# Clock2.net
KiCad netlist of a schematic drawn in EAGLE
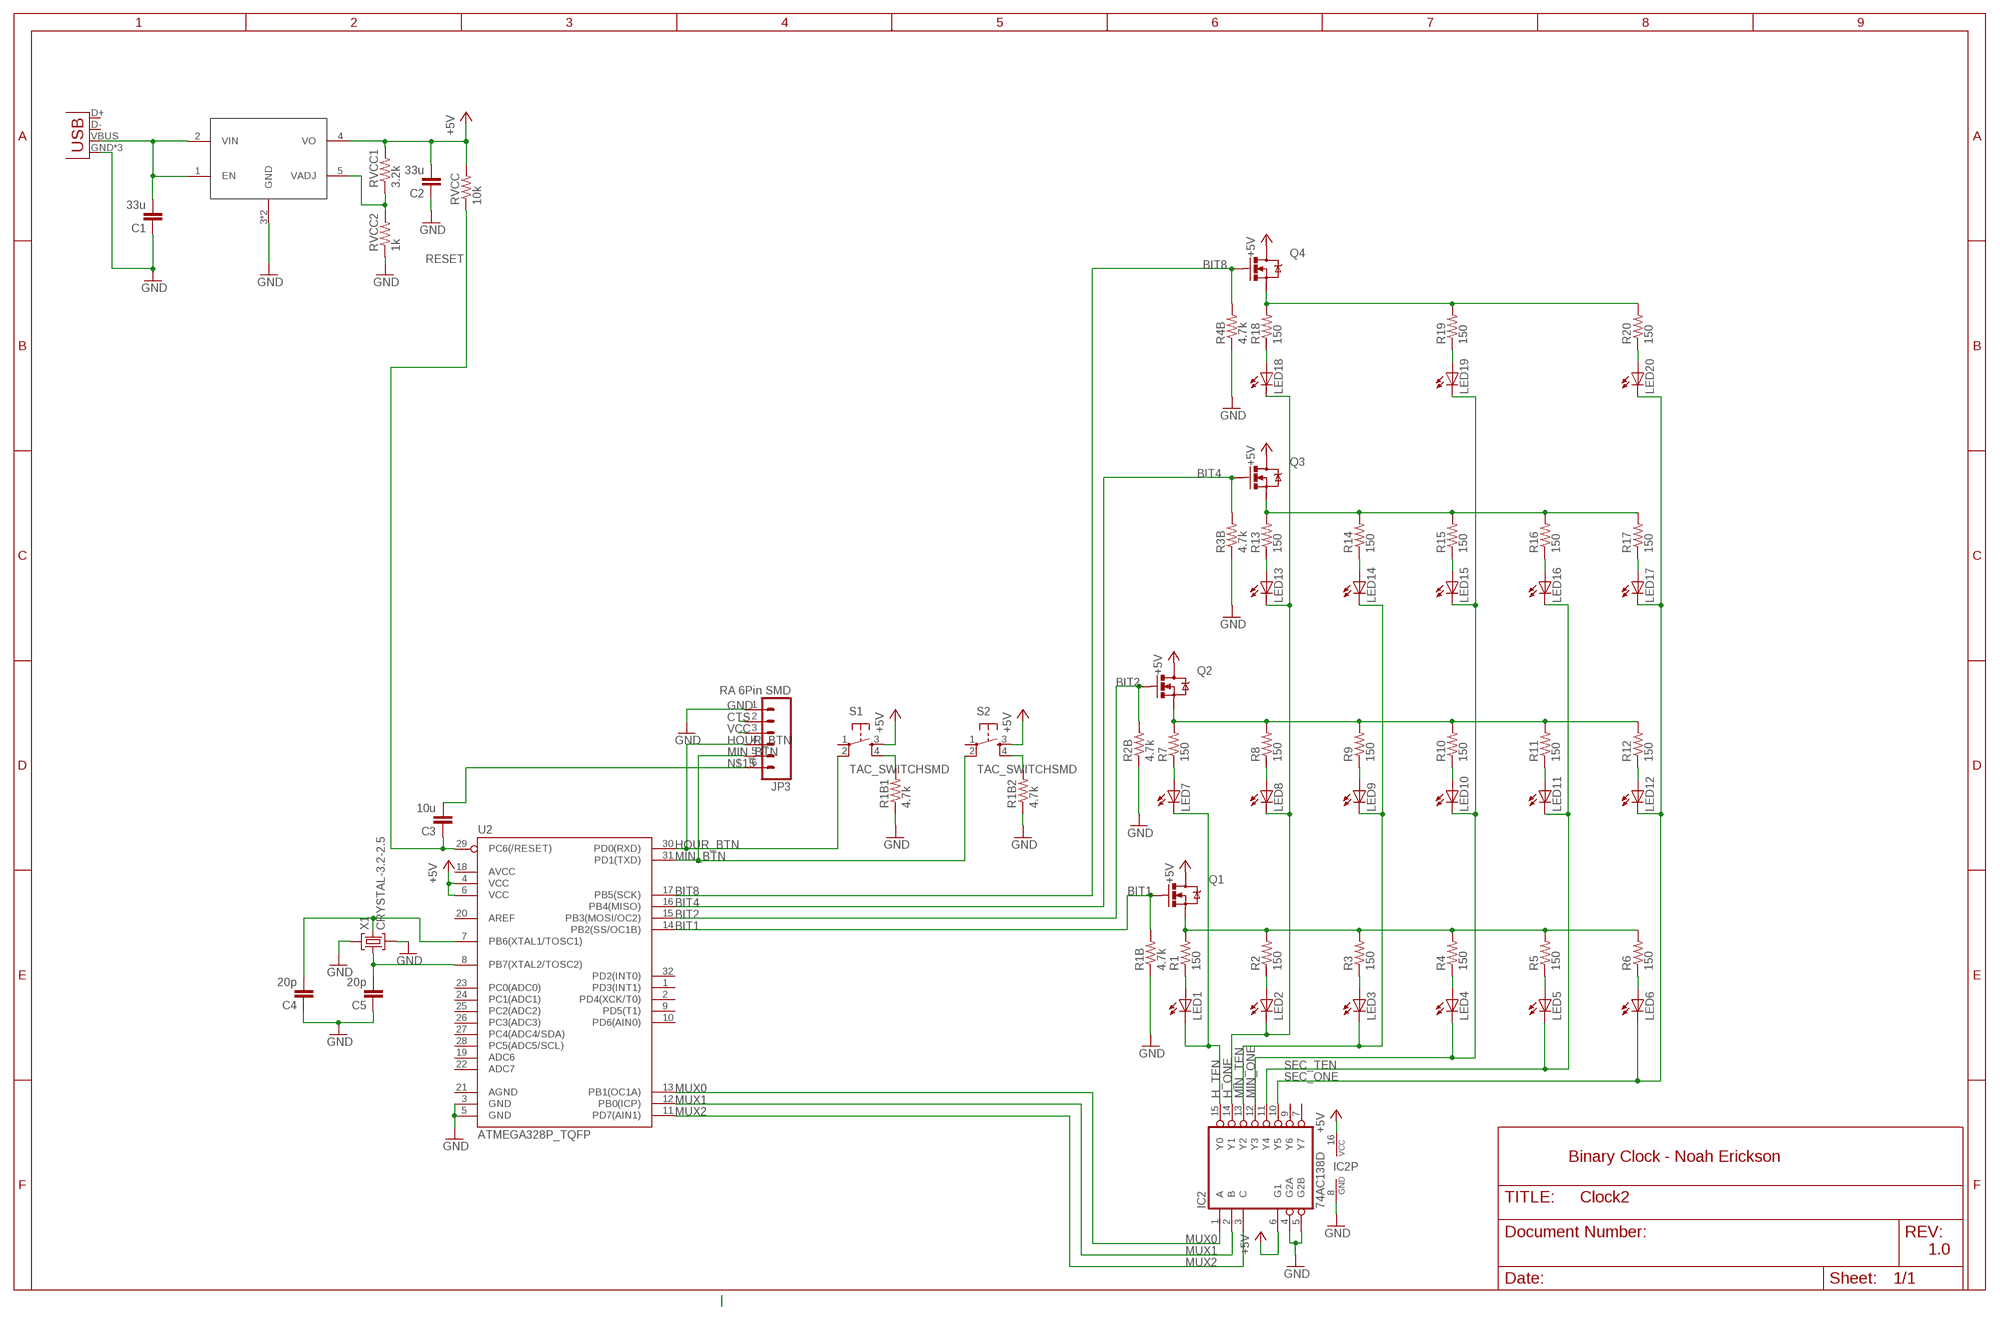
[diagram p0: schematic, sheet 1]

(export (version "E")
  (design (tool "Eeschema 10.0.6"))
  (components
    (comp (ref "C1")
      (value "33u")
      (footprint "eagle-import:C1206")
      (libsource (lib "eagle-import") (part "C-EUC1206"))
    )
    (comp (ref "C2")
      (value "33u")
      (footprint "eagle-import:C1206")
      (libsource (lib "eagle-import") (part "C-EUC1206"))
    )
    (comp (ref "C3")
      (value "10u")
      (footprint "eagle-import:C1206")
      (libsource (lib "eagle-import") (part "C-EUC1206"))
    )
    (comp (ref "C4")
      (value "20p")
      (footprint "eagle-import:C1206")
      (libsource (lib "eagle-import") (part "C-EUC1206"))
    )
    (comp (ref "C5")
      (value "20p")
      (footprint "eagle-import:C1206")
      (libsource (lib "eagle-import") (part "C-EUC1206"))
    )
    (comp (ref "IC2")
      (value "74AC138D")
      (footprint "eagle-import:SO16")
      (libsource (lib "eagle-import") (part "74138DAC"))
    )
    (comp (ref "JP1")
      (value "USB-MICROB")
      (footprint "eagle-import:USB-MICROB")
      (libsource (lib "eagle-import") (part "USB-MICROB"))
    )
    (comp (ref "JP3")
      (value "RA 6Pin SMD")
      (footprint "eagle-import:1X06-SMD")
      (libsource (lib "eagle-import") (part "M06SMD"))
    )
    (comp (ref "LED1")
      (value "LEDSML1206")
      (footprint "eagle-import:SML1206")
      (libsource (lib "eagle-import") (part "LEDSML1206"))
    )
    (comp (ref "LED2")
      (value "LEDSML1206")
      (footprint "eagle-import:SML1206")
      (libsource (lib "eagle-import") (part "LEDSML1206"))
    )
    (comp (ref "LED3")
      (value "LEDSML1206")
      (footprint "eagle-import:SML1206")
      (libsource (lib "eagle-import") (part "LEDSML1206"))
    )
    (comp (ref "LED4")
      (value "LEDSML1206")
      (footprint "eagle-import:SML1206")
      (libsource (lib "eagle-import") (part "LEDSML1206"))
    )
    (comp (ref "LED5")
      (value "LEDSML1206")
      (footprint "eagle-import:SML1206")
      (libsource (lib "eagle-import") (part "LEDSML1206"))
    )
    (comp (ref "LED6")
      (value "LEDSML1206")
      (footprint "eagle-import:SML1206")
      (libsource (lib "eagle-import") (part "LEDSML1206"))
    )
    (comp (ref "LED7")
      (value "LEDSML1206")
      (footprint "eagle-import:SML1206")
      (libsource (lib "eagle-import") (part "LEDSML1206"))
    )
    (comp (ref "LED8")
      (value "LEDSML1206")
      (footprint "eagle-import:SML1206")
      (libsource (lib "eagle-import") (part "LEDSML1206"))
    )
    (comp (ref "LED9")
      (value "LEDSML1206")
      (footprint "eagle-import:SML1206")
      (libsource (lib "eagle-import") (part "LEDSML1206"))
    )
    (comp (ref "LED10")
      (value "LEDSML1206")
      (footprint "eagle-import:SML1206")
      (libsource (lib "eagle-import") (part "LEDSML1206"))
    )
    (comp (ref "LED11")
      (value "LEDSML1206")
      (footprint "eagle-import:SML1206")
      (libsource (lib "eagle-import") (part "LEDSML1206"))
    )
    (comp (ref "LED12")
      (value "LEDSML1206")
      (footprint "eagle-import:SML1206")
      (libsource (lib "eagle-import") (part "LEDSML1206"))
    )
    (comp (ref "LED13")
      (value "LEDSML1206")
      (footprint "eagle-import:SML1206")
      (libsource (lib "eagle-import") (part "LEDSML1206"))
    )
    (comp (ref "LED14")
      (value "LEDSML1206")
      (footprint "eagle-import:SML1206")
      (libsource (lib "eagle-import") (part "LEDSML1206"))
    )
    (comp (ref "LED15")
      (value "LEDSML1206")
      (footprint "eagle-import:SML1206")
      (libsource (lib "eagle-import") (part "LEDSML1206"))
    )
    (comp (ref "LED16")
      (value "LEDSML1206")
      (footprint "eagle-import:SML1206")
      (libsource (lib "eagle-import") (part "LEDSML1206"))
    )
    (comp (ref "LED17")
      (value "LEDSML1206")
      (footprint "eagle-import:SML1206")
      (libsource (lib "eagle-import") (part "LEDSML1206"))
    )
    (comp (ref "LED18")
      (value "LEDSML1206")
      (footprint "eagle-import:SML1206")
      (libsource (lib "eagle-import") (part "LEDSML1206"))
    )
    (comp (ref "LED19")
      (value "LEDSML1206")
      (footprint "eagle-import:SML1206")
      (libsource (lib "eagle-import") (part "LEDSML1206"))
    )
    (comp (ref "LED20")
      (value "LEDSML1206")
      (footprint "eagle-import:SML1206")
      (libsource (lib "eagle-import") (part "LEDSML1206"))
    )
    (comp (ref "Q1")
      (value "MOSFET-NCHANNELBSS138")
      (footprint "eagle-import:SOT23-3")
      (libsource (lib "eagle-import") (part "MOSFET-NCHANNELBSS138"))
    )
    (comp (ref "Q2")
      (value "MOSFET-NCHANNELBSS138")
      (footprint "eagle-import:SOT23-3")
      (libsource (lib "eagle-import") (part "MOSFET-NCHANNELBSS138"))
    )
    (comp (ref "Q3")
      (value "MOSFET-NCHANNELBSS138")
      (footprint "eagle-import:SOT23-3")
      (libsource (lib "eagle-import") (part "MOSFET-NCHANNELBSS138"))
    )
    (comp (ref "Q4")
      (value "MOSFET-NCHANNELBSS138")
      (footprint "eagle-import:SOT23-3")
      (libsource (lib "eagle-import") (part "MOSFET-NCHANNELBSS138"))
    )
    (comp (ref "R1")
      (value "150")
      (footprint "eagle-import:R1206")
      (libsource (lib "eagle-import") (part "R-US_R1206"))
    )
    (comp (ref "R1B")
      (value "4.7k")
      (footprint "eagle-import:R1206")
      (libsource (lib "eagle-import") (part "R-US_R1206"))
    )
    (comp (ref "R1B1")
      (value "4.7k")
      (footprint "eagle-import:R1206")
      (libsource (lib "eagle-import") (part "R-US_R1206"))
    )
    (comp (ref "R1B2")
      (value "4.7k")
      (footprint "eagle-import:R1206")
      (libsource (lib "eagle-import") (part "R-US_R1206"))
    )
    (comp (ref "R2")
      (value "150")
      (footprint "eagle-import:R1206")
      (libsource (lib "eagle-import") (part "R-US_R1206"))
    )
    (comp (ref "R2B")
      (value "4.7k")
      (footprint "eagle-import:R1206")
      (libsource (lib "eagle-import") (part "R-US_R1206"))
    )
    (comp (ref "R3")
      (value "150")
      (footprint "eagle-import:R1206")
      (libsource (lib "eagle-import") (part "R-US_R1206"))
    )
    (comp (ref "R3B")
      (value "4.7k")
      (footprint "eagle-import:R1206")
      (libsource (lib "eagle-import") (part "R-US_R1206"))
    )
    (comp (ref "R4")
      (value "150")
      (footprint "eagle-import:R1206")
      (libsource (lib "eagle-import") (part "R-US_R1206"))
    )
    (comp (ref "R4B")
      (value "4.7k")
      (footprint "eagle-import:R1206")
      (libsource (lib "eagle-import") (part "R-US_R1206"))
    )
    (comp (ref "R5")
      (value "150")
      (footprint "eagle-import:R1206")
      (libsource (lib "eagle-import") (part "R-US_R1206"))
    )
    (comp (ref "R6")
      (value "150")
      (footprint "eagle-import:R1206")
      (libsource (lib "eagle-import") (part "R-US_R1206"))
    )
    (comp (ref "R7")
      (value "150")
      (footprint "eagle-import:R1206")
      (libsource (lib "eagle-import") (part "R-US_R1206"))
    )
    (comp (ref "R8")
      (value "150")
      (footprint "eagle-import:R1206")
      (libsource (lib "eagle-import") (part "R-US_R1206"))
    )
    (comp (ref "R9")
      (value "150")
      (footprint "eagle-import:R1206")
      (libsource (lib "eagle-import") (part "R-US_R1206"))
    )
    (comp (ref "R10")
      (value "150")
      (footprint "eagle-import:R1206")
      (libsource (lib "eagle-import") (part "R-US_R1206"))
    )
    (comp (ref "R11")
      (value "150")
      (footprint "eagle-import:R1206")
      (libsource (lib "eagle-import") (part "R-US_R1206"))
    )
    (comp (ref "R12")
      (value "150")
      (footprint "eagle-import:R1206")
      (libsource (lib "eagle-import") (part "R-US_R1206"))
    )
    (comp (ref "R13")
      (value "150")
      (footprint "eagle-import:R1206")
      (libsource (lib "eagle-import") (part "R-US_R1206"))
    )
    (comp (ref "R14")
      (value "150")
      (footprint "eagle-import:R1206")
      (libsource (lib "eagle-import") (part "R-US_R1206"))
    )
    (comp (ref "R15")
      (value "150")
      (footprint "eagle-import:R1206")
      (libsource (lib "eagle-import") (part "R-US_R1206"))
    )
    (comp (ref "R16")
      (value "150")
      (footprint "eagle-import:R1206")
      (libsource (lib "eagle-import") (part "R-US_R1206"))
    )
    (comp (ref "R17")
      (value "150")
      (footprint "eagle-import:R1206")
      (libsource (lib "eagle-import") (part "R-US_R1206"))
    )
    (comp (ref "R18")
      (value "150")
      (footprint "eagle-import:R1206")
      (libsource (lib "eagle-import") (part "R-US_R1206"))
    )
    (comp (ref "R19")
      (value "150")
      (footprint "eagle-import:R1206")
      (libsource (lib "eagle-import") (part "R-US_R1206"))
    )
    (comp (ref "R20")
      (value "150")
      (footprint "eagle-import:R1206")
      (libsource (lib "eagle-import") (part "R-US_R1206"))
    )
    (comp (ref "RVCC")
      (value "10k")
      (footprint "eagle-import:R1206")
      (libsource (lib "eagle-import") (part "R-US_R1206"))
    )
    (comp (ref "RVCC1")
      (value "3.2k")
      (footprint "eagle-import:R1206")
      (libsource (lib "eagle-import") (part "R-US_R1206"))
    )
    (comp (ref "RVCC2")
      (value "1k")
      (footprint "eagle-import:R1206")
      (libsource (lib "eagle-import") (part "R-US_R1206"))
    )
    (comp (ref "S1")
      (value "TAC_SWITCHSMD")
      (footprint "eagle-import:TACTILE-SWITCH-SMD")
      (libsource (lib "eagle-import") (part "TAC_SWITCHSMD"))
    )
    (comp (ref "S2")
      (value "TAC_SWITCHSMD")
      (footprint "eagle-import:TACTILE-SWITCH-SMD")
      (libsource (lib "eagle-import") (part "TAC_SWITCHSMD"))
    )
    (comp (ref "U$1")
      (value "TLF1963")
      (footprint "eagle-import:DPAK")
      (libsource (lib "eagle-import") (part "TLF1963"))
    )
    (comp (ref "U2")
      (value "ATMEGA328P_TQFP")
      (footprint "eagle-import:TQFP32-08")
      (libsource (lib "eagle-import") (part "ATMEGA328P_TQFP"))
    )
    (comp (ref "X1")
      (value "CRYSTAL-3.2-2.5")
      (footprint "eagle-import:CRYSTAL-3.2-2.5")
      (libsource (lib "eagle-import") (part "CRYSTAL-3.2-2.5"))
    )
  )
  (nets
    (net (code "1") (name "+5V") (class "Default")
      (node (ref "C2") (pin "2") (pinfunction "2_2") (pintype "passive"))
      (node (ref "IC2") (pin "16") (pinfunction "VCC_16") (pintype "power_in"))
      (node (ref "IC2") (pin "6") (pinfunction "G1_6") (pintype "input"))
      (node (ref "Q1") (pin "3") (pinfunction "D_3") (pintype "passive"))
      (node (ref "Q2") (pin "3") (pinfunction "D_3") (pintype "passive"))
      (node (ref "Q3") (pin "3") (pinfunction "D_3") (pintype "passive"))
      (node (ref "Q4") (pin "3") (pinfunction "D_3") (pintype "passive"))
      (node (ref "RVCC") (pin "2") (pinfunction "2_2") (pintype "passive"))
      (node (ref "RVCC1") (pin "2") (pinfunction "2_2") (pintype "passive"))
      (node (ref "S1") (pin "3") (pinfunction "3_3") (pintype "passive"))
      (node (ref "S2") (pin "3") (pinfunction "3_3") (pintype "passive"))
      (node (ref "U$1") (pin "4") (pinfunction "VO_4") (pintype "bidirectional"))
      (node (ref "U2") (pin "4") (pinfunction "VCC_4") (pintype "bidirectional"))
      (node (ref "U2") (pin "6") (pinfunction "VCC_6") (pintype "bidirectional"))
    )
    (net (code "2") (name "/BIT1") (class "Default")
      (node (ref "Q1") (pin "1") (pinfunction "G_1") (pintype "passive"))
      (node (ref "R1B") (pin "2") (pinfunction "2_2") (pintype "passive"))
      (node (ref "U2") (pin "14") (pinfunction "PB2(SS/OC1B)_14") (pintype "bidirectional"))
    )
    (net (code "3") (name "/BIT2") (class "Default")
      (node (ref "Q2") (pin "1") (pinfunction "G_1") (pintype "passive"))
      (node (ref "R2B") (pin "2") (pinfunction "2_2") (pintype "passive"))
      (node (ref "U2") (pin "15") (pinfunction "PB3(MOSI/OC2)_15") (pintype "bidirectional"))
    )
    (net (code "4") (name "/BIT4") (class "Default")
      (node (ref "Q3") (pin "1") (pinfunction "G_1") (pintype "passive"))
      (node (ref "R3B") (pin "2") (pinfunction "2_2") (pintype "passive"))
      (node (ref "U2") (pin "16") (pinfunction "PB4(MISO)_16") (pintype "bidirectional"))
    )
    (net (code "5") (name "/BIT8") (class "Default")
      (node (ref "Q4") (pin "1") (pinfunction "G_1") (pintype "passive"))
      (node (ref "R4B") (pin "2") (pinfunction "2_2") (pintype "passive"))
      (node (ref "U2") (pin "17") (pinfunction "PB5(SCK)_17") (pintype "bidirectional"))
    )
    (net (code "6") (name "/CTS") (class "Default")
      (node (ref "JP3") (pin "2") (pinfunction "2_2") (pintype "passive"))
    )
    (net (code "7") (name "/HOUR_BTN") (class "Default")
      (node (ref "JP3") (pin "4") (pinfunction "4_4") (pintype "passive"))
      (node (ref "S1") (pin "2") (pinfunction "2_2") (pintype "passive"))
      (node (ref "U2") (pin "30") (pinfunction "PD0(RXD)_30") (pintype "bidirectional"))
    )
    (net (code "8") (name "/H_ONE") (class "Default")
      (node (ref "IC2") (pin "14") (pinfunction "Y1_14") (pintype "output"))
      (node (ref "LED13") (pin "C") (pinfunction "C_C") (pintype "passive"))
      (node (ref "LED18") (pin "C") (pinfunction "C_C") (pintype "passive"))
      (node (ref "LED2") (pin "C") (pinfunction "C_C") (pintype "passive"))
      (node (ref "LED8") (pin "C") (pinfunction "C_C") (pintype "passive"))
    )
    (net (code "9") (name "/H_TEN") (class "Default")
      (node (ref "IC2") (pin "15") (pinfunction "Y0_15") (pintype "output"))
      (node (ref "LED1") (pin "C") (pinfunction "C_C") (pintype "passive"))
      (node (ref "LED7") (pin "C") (pinfunction "C_C") (pintype "passive"))
    )
    (net (code "10") (name "/MIN_BTN") (class "Default")
      (node (ref "JP3") (pin "5") (pinfunction "5_5") (pintype "passive"))
      (node (ref "S2") (pin "2") (pinfunction "2_2") (pintype "passive"))
      (node (ref "U2") (pin "31") (pinfunction "PD1(TXD)_31") (pintype "bidirectional"))
    )
    (net (code "11") (name "/MIN_ONE") (class "Default")
      (node (ref "IC2") (pin "12") (pinfunction "Y3_12") (pintype "output"))
      (node (ref "LED10") (pin "C") (pinfunction "C_C") (pintype "passive"))
      (node (ref "LED15") (pin "C") (pinfunction "C_C") (pintype "passive"))
      (node (ref "LED19") (pin "C") (pinfunction "C_C") (pintype "passive"))
      (node (ref "LED4") (pin "C") (pinfunction "C_C") (pintype "passive"))
    )
    (net (code "12") (name "/MIN_TEN") (class "Default")
      (node (ref "IC2") (pin "13") (pinfunction "Y2_13") (pintype "output"))
      (node (ref "LED14") (pin "C") (pinfunction "C_C") (pintype "passive"))
      (node (ref "LED3") (pin "C") (pinfunction "C_C") (pintype "passive"))
      (node (ref "LED9") (pin "C") (pinfunction "C_C") (pintype "passive"))
    )
    (net (code "13") (name "/MUX0") (class "Default")
      (node (ref "IC2") (pin "1") (pinfunction "A_1") (pintype "input"))
      (node (ref "U2") (pin "13") (pinfunction "PB1(OC1A)_13") (pintype "bidirectional"))
    )
    (net (code "14") (name "/MUX1") (class "Default")
      (node (ref "IC2") (pin "2") (pinfunction "B_2") (pintype "input"))
      (node (ref "U2") (pin "12") (pinfunction "PB0(ICP)_12") (pintype "bidirectional"))
    )
    (net (code "15") (name "/MUX2") (class "Default")
      (node (ref "IC2") (pin "3") (pinfunction "C_3") (pintype "input"))
      (node (ref "U2") (pin "11") (pinfunction "PD7(AIN1)_11") (pintype "bidirectional"))
    )
    (net (code "16") (name "/N$15") (class "Default")
      (node (ref "C3") (pin "2") (pinfunction "2_2") (pintype "passive"))
      (node (ref "JP3") (pin "6") (pinfunction "6_6") (pintype "passive"))
    )
    (net (code "17") (name "/RESET") (class "Default")
      (node (ref "C3") (pin "1") (pinfunction "1_1") (pintype "passive"))
      (node (ref "RVCC") (pin "1") (pinfunction "1_1") (pintype "passive"))
      (node (ref "U2") (pin "29") (pinfunction "PC6(/RESET)_29") (pintype "bidirectional"))
    )
    (net (code "18") (name "/SEC_ONE") (class "Default")
      (node (ref "IC2") (pin "10") (pinfunction "Y5_10") (pintype "output"))
      (node (ref "LED12") (pin "C") (pinfunction "C_C") (pintype "passive"))
      (node (ref "LED17") (pin "C") (pinfunction "C_C") (pintype "passive"))
      (node (ref "LED20") (pin "C") (pinfunction "C_C") (pintype "passive"))
      (node (ref "LED6") (pin "C") (pinfunction "C_C") (pintype "passive"))
    )
    (net (code "19") (name "/SEC_TEN") (class "Default")
      (node (ref "IC2") (pin "11") (pinfunction "Y4_11") (pintype "output"))
      (node (ref "LED11") (pin "C") (pinfunction "C_C") (pintype "passive"))
      (node (ref "LED16") (pin "C") (pinfunction "C_C") (pintype "passive"))
      (node (ref "LED5") (pin "C") (pinfunction "C_C") (pintype "passive"))
    )
    (net (code "20") (name "/VCC") (class "Default")
      (node (ref "JP3") (pin "3") (pinfunction "3_3") (pintype "passive"))
    )
    (net (code "21") (name "GND") (class "Default")
      (node (ref "C1") (pin "1") (pinfunction "1_1") (pintype "passive"))
      (node (ref "C2") (pin "1") (pinfunction "1_1") (pintype "passive"))
      (node (ref "C4") (pin "1") (pinfunction "1_1") (pintype "passive"))
      (node (ref "C5") (pin "1") (pinfunction "1_1") (pintype "passive"))
      (node (ref "IC2") (pin "4") (pinfunction "G2A_4") (pintype "input"))
      (node (ref "IC2") (pin "5") (pinfunction "G2B_5") (pintype "input"))
      (node (ref "IC2") (pin "8") (pinfunction "GND_8") (pintype "power_in"))
      (node (ref "JP1") (pin "GND") (pinfunction "GND_GND") (pintype "bidirectional"))
      (node (ref "JP1") (pin "MT1") (pinfunction "GND_MT1") (pintype "bidirectional"))
      (node (ref "JP1") (pin "MT2") (pinfunction "GND_MT2") (pintype "bidirectional"))
      (node (ref "JP3") (pin "1") (pinfunction "1_1") (pintype "passive"))
      (node (ref "R1B") (pin "1") (pinfunction "1_1") (pintype "passive"))
      (node (ref "R1B1") (pin "1") (pinfunction "1_1") (pintype "passive"))
      (node (ref "R1B2") (pin "1") (pinfunction "1_1") (pintype "passive"))
      (node (ref "R2B") (pin "1") (pinfunction "1_1") (pintype "passive"))
      (node (ref "R3B") (pin "1") (pinfunction "1_1") (pintype "passive"))
      (node (ref "R4B") (pin "1") (pinfunction "1_1") (pintype "passive"))
      (node (ref "RVCC2") (pin "1") (pinfunction "1_1") (pintype "passive"))
      (node (ref "U$1") (pin "3") (pinfunction "GND_3") (pintype "bidirectional"))
      (node (ref "U$1") (pin "6") (pinfunction "GND_6") (pintype "bidirectional"))
      (node (ref "U2") (pin "3") (pinfunction "GND_3") (pintype "bidirectional"))
      (node (ref "U2") (pin "5") (pinfunction "GND_5") (pintype "bidirectional"))
      (node (ref "X1") (pin "2") (pinfunction "GND_2") (pintype "passive"))
      (node (ref "X1") (pin "4") (pinfunction "GND_4") (pintype "passive"))
    )
    (net (code "22") (name "Net-(LED1-PadA)") (class "Default")
      (node (ref "LED1") (pin "A") (pinfunction "A_A") (pintype "passive"))
      (node (ref "R1") (pin "1") (pinfunction "1_1") (pintype "passive"))
    )
    (net (code "23") (name "Net-(LED2-PadA)") (class "Default")
      (node (ref "LED2") (pin "A") (pinfunction "A_A") (pintype "passive"))
      (node (ref "R2") (pin "1") (pinfunction "1_1") (pintype "passive"))
    )
    (net (code "24") (name "Net-(LED3-PadA)") (class "Default")
      (node (ref "LED3") (pin "A") (pinfunction "A_A") (pintype "passive"))
      (node (ref "R3") (pin "1") (pinfunction "1_1") (pintype "passive"))
    )
    (net (code "25") (name "Net-(LED4-PadA)") (class "Default")
      (node (ref "LED4") (pin "A") (pinfunction "A_A") (pintype "passive"))
      (node (ref "R4") (pin "1") (pinfunction "1_1") (pintype "passive"))
    )
    (net (code "26") (name "Net-(LED5-PadA)") (class "Default")
      (node (ref "LED5") (pin "A") (pinfunction "A_A") (pintype "passive"))
      (node (ref "R5") (pin "1") (pinfunction "1_1") (pintype "passive"))
    )
    (net (code "27") (name "Net-(LED6-PadA)") (class "Default")
      (node (ref "LED6") (pin "A") (pinfunction "A_A") (pintype "passive"))
      (node (ref "R6") (pin "1") (pinfunction "1_1") (pintype "passive"))
    )
    (net (code "28") (name "Net-(LED7-PadA)") (class "Default")
      (node (ref "LED7") (pin "A") (pinfunction "A_A") (pintype "passive"))
      (node (ref "R7") (pin "1") (pinfunction "1_1") (pintype "passive"))
    )
    (net (code "29") (name "Net-(LED8-PadA)") (class "Default")
      (node (ref "LED8") (pin "A") (pinfunction "A_A") (pintype "passive"))
      (node (ref "R8") (pin "1") (pinfunction "1_1") (pintype "passive"))
    )
    (net (code "30") (name "Net-(LED9-PadA)") (class "Default")
      (node (ref "LED9") (pin "A") (pinfunction "A_A") (pintype "passive"))
      (node (ref "R9") (pin "1") (pinfunction "1_1") (pintype "passive"))
    )
    (net (code "31") (name "Net-(LED10-PadA)") (class "Default")
      (node (ref "LED10") (pin "A") (pinfunction "A_A") (pintype "passive"))
      (node (ref "R10") (pin "1") (pinfunction "1_1") (pintype "passive"))
    )
    (net (code "32") (name "Net-(LED11-PadA)") (class "Default")
      (node (ref "LED11") (pin "A") (pinfunction "A_A") (pintype "passive"))
      (node (ref "R11") (pin "1") (pinfunction "1_1") (pintype "passive"))
    )
    (net (code "33") (name "Net-(LED12-PadA)") (class "Default")
      (node (ref "LED12") (pin "A") (pinfunction "A_A") (pintype "passive"))
      (node (ref "R12") (pin "1") (pinfunction "1_1") (pintype "passive"))
    )
    (net (code "34") (name "Net-(LED13-PadA)") (class "Default")
      (node (ref "LED13") (pin "A") (pinfunction "A_A") (pintype "passive"))
      (node (ref "R13") (pin "1") (pinfunction "1_1") (pintype "passive"))
    )
    (net (code "35") (name "Net-(LED14-PadA)") (class "Default")
      (node (ref "LED14") (pin "A") (pinfunction "A_A") (pintype "passive"))
      (node (ref "R14") (pin "1") (pinfunction "1_1") (pintype "passive"))
    )
    (net (code "36") (name "Net-(LED15-PadA)") (class "Default")
      (node (ref "LED15") (pin "A") (pinfunction "A_A") (pintype "passive"))
      (node (ref "R15") (pin "1") (pinfunction "1_1") (pintype "passive"))
    )
    (net (code "37") (name "Net-(LED16-PadA)") (class "Default")
      (node (ref "LED16") (pin "A") (pinfunction "A_A") (pintype "passive"))
      (node (ref "R16") (pin "1") (pinfunction "1_1") (pintype "passive"))
    )
    (net (code "38") (name "Net-(LED17-PadA)") (class "Default")
      (node (ref "LED17") (pin "A") (pinfunction "A_A") (pintype "passive"))
      (node (ref "R17") (pin "1") (pinfunction "1_1") (pintype "passive"))
    )
    (net (code "39") (name "Net-(LED18-PadA)") (class "Default")
      (node (ref "LED18") (pin "A") (pinfunction "A_A") (pintype "passive"))
      (node (ref "R18") (pin "1") (pinfunction "1_1") (pintype "passive"))
    )
    (net (code "40") (name "Net-(LED19-PadA)") (class "Default")
      (node (ref "LED19") (pin "A") (pinfunction "A_A") (pintype "passive"))
      (node (ref "R19") (pin "1") (pinfunction "1_1") (pintype "passive"))
    )
    (net (code "41") (name "Net-(LED20-PadA)") (class "Default")
      (node (ref "LED20") (pin "A") (pinfunction "A_A") (pintype "passive"))
      (node (ref "R20") (pin "1") (pinfunction "1_1") (pintype "passive"))
    )
    (net (code "42") (name "Net-(Q1-S)") (class "Default")
      (node (ref "Q1") (pin "2") (pinfunction "S_2") (pintype "passive"))
      (node (ref "R1") (pin "2") (pinfunction "2_2") (pintype "passive"))
      (node (ref "R2") (pin "2") (pinfunction "2_2") (pintype "passive"))
      (node (ref "R3") (pin "2") (pinfunction "2_2") (pintype "passive"))
      (node (ref "R4") (pin "2") (pinfunction "2_2") (pintype "passive"))
      (node (ref "R5") (pin "2") (pinfunction "2_2") (pintype "passive"))
      (node (ref "R6") (pin "2") (pinfunction "2_2") (pintype "passive"))
    )
    (net (code "43") (name "Net-(Q2-S)") (class "Default")
      (node (ref "Q2") (pin "2") (pinfunction "S_2") (pintype "passive"))
      (node (ref "R10") (pin "2") (pinfunction "2_2") (pintype "passive"))
      (node (ref "R11") (pin "2") (pinfunction "2_2") (pintype "passive"))
      (node (ref "R12") (pin "2") (pinfunction "2_2") (pintype "passive"))
      (node (ref "R7") (pin "2") (pinfunction "2_2") (pintype "passive"))
      (node (ref "R8") (pin "2") (pinfunction "2_2") (pintype "passive"))
      (node (ref "R9") (pin "2") (pinfunction "2_2") (pintype "passive"))
    )
    (net (code "44") (name "Net-(Q3-S)") (class "Default")
      (node (ref "Q3") (pin "2") (pinfunction "S_2") (pintype "passive"))
      (node (ref "R13") (pin "2") (pinfunction "2_2") (pintype "passive"))
      (node (ref "R14") (pin "2") (pinfunction "2_2") (pintype "passive"))
      (node (ref "R15") (pin "2") (pinfunction "2_2") (pintype "passive"))
      (node (ref "R16") (pin "2") (pinfunction "2_2") (pintype "passive"))
      (node (ref "R17") (pin "2") (pinfunction "2_2") (pintype "passive"))
    )
    (net (code "45") (name "Net-(Q4-S)") (class "Default")
      (node (ref "Q4") (pin "2") (pinfunction "S_2") (pintype "passive"))
      (node (ref "R18") (pin "2") (pinfunction "2_2") (pintype "passive"))
      (node (ref "R19") (pin "2") (pinfunction "2_2") (pintype "passive"))
      (node (ref "R20") (pin "2") (pinfunction "2_2") (pintype "passive"))
    )
    (net (code "46") (name "Net-(R1B1-Pad2)") (class "Default")
      (node (ref "R1B1") (pin "2") (pinfunction "2_2") (pintype "passive"))
      (node (ref "S1") (pin "4") (pinfunction "4_4") (pintype "passive"))
    )
    (net (code "47") (name "Net-(R1B2-Pad2)") (class "Default")
      (node (ref "R1B2") (pin "2") (pinfunction "2_2") (pintype "passive"))
      (node (ref "S2") (pin "4") (pinfunction "4_4") (pintype "passive"))
    )
    (net (code "48") (name "Net-(U$1-EN)") (class "Default")
      (node (ref "C1") (pin "2") (pinfunction "2_2") (pintype "passive"))
      (node (ref "JP1") (pin "VBUS") (pinfunction "VBUS_VBUS") (pintype "bidirectional"))
      (node (ref "U$1") (pin "1") (pinfunction "EN_1") (pintype "bidirectional"))
      (node (ref "U$1") (pin "2") (pinfunction "VIN_2") (pintype "bidirectional"))
    )
    (net (code "49") (name "Net-(U$1-VADJ)") (class "Default")
      (node (ref "RVCC1") (pin "1") (pinfunction "1_1") (pintype "passive"))
      (node (ref "RVCC2") (pin "2") (pinfunction "2_2") (pintype "passive"))
      (node (ref "U$1") (pin "5") (pinfunction "VADJ_5") (pintype "bidirectional"))
    )
    (net (code "50") (name "Net-(U2-PB6(XTAL1{slash}TOSC1))") (class "Default")
      (node (ref "C4") (pin "2") (pinfunction "2_2") (pintype "passive"))
      (node (ref "U2") (pin "7") (pinfunction "PB6(XTAL1/TOSC1)_7") (pintype "bidirectional"))
      (node (ref "X1") (pin "3") (pinfunction "C2_3") (pintype "passive"))
    )
    (net (code "51") (name "Net-(U2-PB7(XTAL2{slash}TOSC2))") (class "Default")
      (node (ref "C5") (pin "2") (pinfunction "2_2") (pintype "passive"))
      (node (ref "U2") (pin "8") (pinfunction "PB7(XTAL2/TOSC2)_8") (pintype "bidirectional"))
      (node (ref "X1") (pin "1") (pinfunction "C1_1") (pintype "passive"))
    )
    (net (code "52") (name "unconnected-(IC2A-Y6-Pad9)") (class "Default")
      (node (ref "IC2") (pin "9") (pinfunction "Y6_9") (pintype "output"))
    )
    (net (code "53") (name "unconnected-(IC2A-Y7-Pad7)") (class "Default")
      (node (ref "IC2") (pin "7") (pinfunction "Y7_7") (pintype "output"))
    )
    (net (code "54") (name "unconnected-(JP1-PadD+)") (class "Default")
      (node (ref "JP1") (pin "D+") (pinfunction "D+_D+") (pintype "bidirectional"))
    )
    (net (code "55") (name "unconnected-(JP1-PadD-)") (class "Default")
      (node (ref "JP1") (pin "D-") (pinfunction "D-_D-") (pintype "bidirectional"))
    )
    (net (code "56") (name "unconnected-(S1-Pad1)") (class "Default")
      (node (ref "S1") (pin "1") (pinfunction "1_1") (pintype "passive"))
    )
    (net (code "57") (name "unconnected-(S2-Pad1)") (class "Default")
      (node (ref "S2") (pin "1") (pinfunction "1_1") (pintype "passive"))
    )
    (net (code "58") (name "unconnected-(U2-ADC6-Pad19)") (class "Default")
      (node (ref "U2") (pin "19") (pinfunction "ADC6_19") (pintype "bidirectional"))
    )
    (net (code "59") (name "unconnected-(U2-ADC7-Pad22)") (class "Default")
      (node (ref "U2") (pin "22") (pinfunction "ADC7_22") (pintype "bidirectional"))
    )
    (net (code "60") (name "unconnected-(U2-AGND-Pad21)") (class "Default")
      (node (ref "U2") (pin "21") (pinfunction "AGND_21") (pintype "bidirectional"))
    )
    (net (code "61") (name "unconnected-(U2-AREF-Pad20)") (class "Default")
      (node (ref "U2") (pin "20") (pinfunction "AREF_20") (pintype "bidirectional"))
    )
    (net (code "62") (name "unconnected-(U2-AVCC-Pad18)") (class "Default")
      (node (ref "U2") (pin "18") (pinfunction "AVCC_18") (pintype "bidirectional"))
    )
    (net (code "63") (name "unconnected-(U2-PC0(ADC0)-Pad23)") (class "Default")
      (node (ref "U2") (pin "23") (pinfunction "PC0(ADC0)_23") (pintype "bidirectional"))
    )
    (net (code "64") (name "unconnected-(U2-PC1(ADC1)-Pad24)") (class "Default")
      (node (ref "U2") (pin "24") (pinfunction "PC1(ADC1)_24") (pintype "bidirectional"))
    )
    (net (code "65") (name "unconnected-(U2-PC2(ADC2)-Pad25)") (class "Default")
      (node (ref "U2") (pin "25") (pinfunction "PC2(ADC2)_25") (pintype "bidirectional"))
    )
    (net (code "66") (name "unconnected-(U2-PC3(ADC3)-Pad26)") (class "Default")
      (node (ref "U2") (pin "26") (pinfunction "PC3(ADC3)_26") (pintype "bidirectional"))
    )
    (net (code "67") (name "unconnected-(U2-PC4(ADC4{slash}SDA)-Pad27)") (class "Default")
      (node (ref "U2") (pin "27") (pinfunction "PC4(ADC4/SDA)_27") (pintype "bidirectional"))
    )
    (net (code "68") (name "unconnected-(U2-PC5(ADC5{slash}SCL)-Pad28)") (class "Default")
      (node (ref "U2") (pin "28") (pinfunction "PC5(ADC5/SCL)_28") (pintype "bidirectional"))
    )
    (net (code "69") (name "unconnected-(U2-PD2(INT0)-Pad32)") (class "Default")
      (node (ref "U2") (pin "32") (pinfunction "PD2(INT0)_32") (pintype "bidirectional"))
    )
    (net (code "70") (name "unconnected-(U2-PD3(INT1)-Pad1)") (class "Default")
      (node (ref "U2") (pin "1") (pinfunction "PD3(INT1)_1") (pintype "bidirectional"))
    )
    (net (code "71") (name "unconnected-(U2-PD4(XCK{slash}T0)-Pad2)") (class "Default")
      (node (ref "U2") (pin "2") (pinfunction "PD4(XCK/T0)_2") (pintype "bidirectional"))
    )
    (net (code "72") (name "unconnected-(U2-PD5(T1)-Pad9)") (class "Default")
      (node (ref "U2") (pin "9") (pinfunction "PD5(T1)_9") (pintype "bidirectional"))
    )
    (net (code "73") (name "unconnected-(U2-PD6(AIN0)-Pad10)") (class "Default")
      (node (ref "U2") (pin "10") (pinfunction "PD6(AIN0)_10") (pintype "bidirectional"))
    )
  )
)
